# PAM2401_Tester.net
KiCad netlist of a schematic drawn in EAGLE
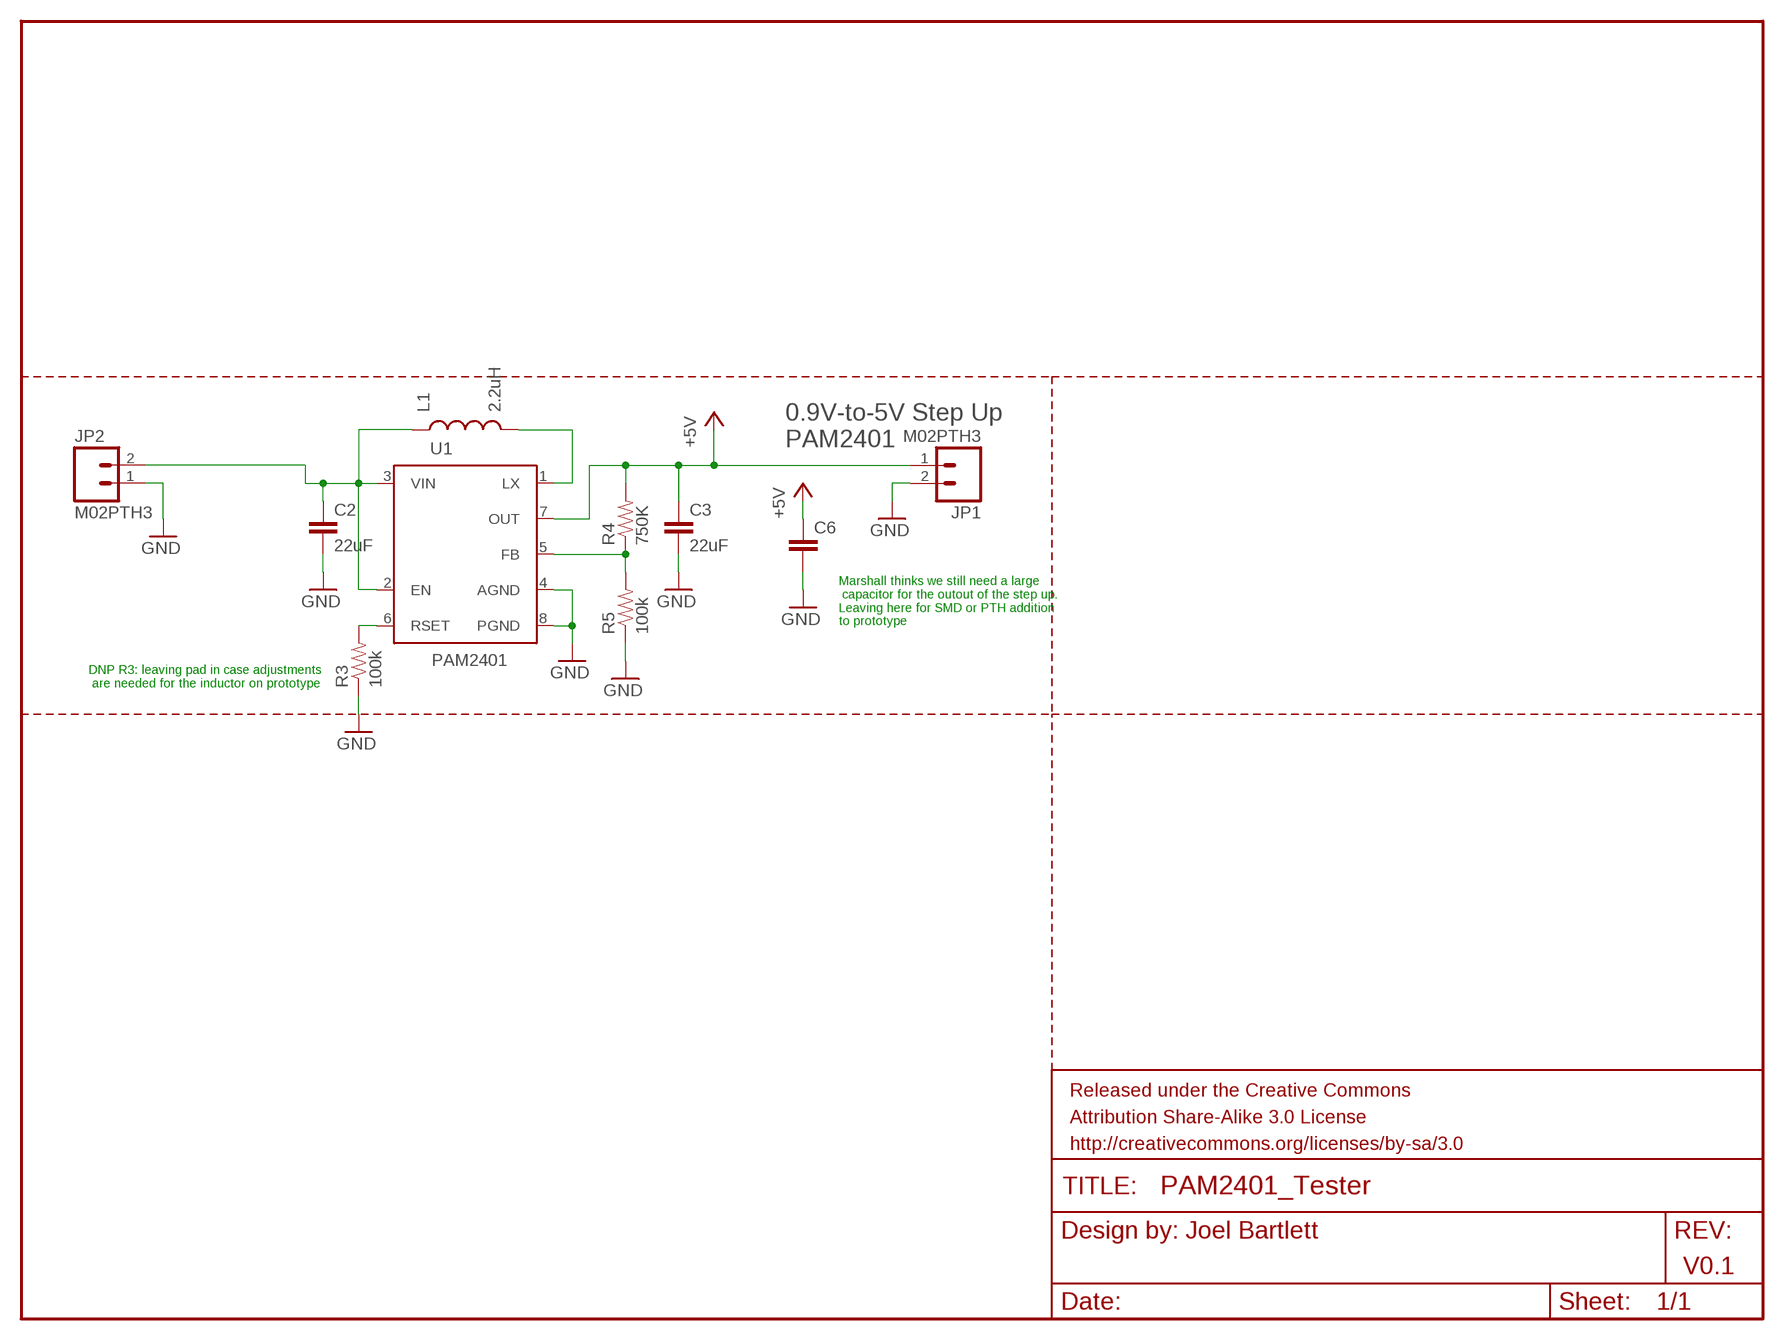
[diagram p0: schematic, sheet 1]

(export (version "E")
  (design (tool "Eeschema 10.0.6"))
  (components
    (comp (ref "C2")
      (value "22uF")
      (footprint "eagle-import:0805")
      (libsource (lib "eagle-import") (part "22UF-6.3V-20%(0805)"))
    )
    (comp (ref "C3")
      (value "22uF")
      (footprint "eagle-import:0805")
      (libsource (lib "eagle-import") (part "22UF-6.3V-20%(0805)"))
    )
    (comp (ref "C6")
      (value "CAP1206")
      (footprint "eagle-import:1206")
      (libsource (lib "eagle-import") (part "CAP1206"))
    )
    (comp (ref "FRAME1")
      (value "FRAME-LETTER")
      (footprint "eagle-import:CREATIVE_COMMONS")
      (libsource (lib "eagle-import") (part "FRAME-LETTER"))
    )
    (comp (ref "JP1")
      (value "M02PTH3")
      (footprint "eagle-import:1X02_LONGPADS")
      (libsource (lib "eagle-import") (part "M02PTH3"))
    )
    (comp (ref "JP2")
      (value "M02PTH3")
      (footprint "eagle-import:1X02_LONGPADS")
      (libsource (lib "eagle-import") (part "M02PTH3"))
    )
    (comp (ref "L1")
      (value "2.2uH")
      (footprint "eagle-import:CR54")
      (libsource (lib "eagle-import") (part "INDUCTORCR54"))
    )
    (comp (ref "R3")
      (value "100k")
      (footprint "eagle-import:0603-RES")
      (libsource (lib "eagle-import") (part "10K-1%RES-00824"))
    )
    (comp (ref "R4")
      (value "750K")
      (footprint "eagle-import:0603-RES")
      (libsource (lib "eagle-import") (part "10K-1%RES-00824"))
    )
    (comp (ref "R5")
      (value "100k")
      (footprint "eagle-import:0603-RES")
      (libsource (lib "eagle-import") (part "10K-1%RES-00824"))
    )
    (comp (ref "U1")
      (value "PAM2401")
      (footprint "eagle-import:MSOP8")
      (libsource (lib "eagle-import") (part "PAM2401"))
    )
  )
  (nets
    (net (code "1") (name "+5V") (class "Default")
      (node (ref "C3") (pin "1") (pinfunction "1_1") (pintype "passive"))
      (node (ref "C6") (pin "1") (pinfunction "1_1") (pintype "passive"))
      (node (ref "JP1") (pin "1") (pinfunction "1_1") (pintype "passive"))
      (node (ref "R4") (pin "2") (pinfunction "2_2") (pintype "passive"))
      (node (ref "U1") (pin "7") (pinfunction "OUT_7") (pintype "bidirectional"))
    )
    (net (code "2") (name "GND") (class "Default")
      (node (ref "C2") (pin "2") (pinfunction "2_2") (pintype "passive"))
      (node (ref "C3") (pin "2") (pinfunction "2_2") (pintype "passive"))
      (node (ref "C6") (pin "2") (pinfunction "2_2") (pintype "passive"))
      (node (ref "JP1") (pin "2") (pinfunction "2_2") (pintype "passive"))
      (node (ref "JP2") (pin "1") (pinfunction "1_1") (pintype "passive"))
      (node (ref "R3") (pin "1") (pinfunction "1_1") (pintype "passive"))
      (node (ref "R5") (pin "1") (pinfunction "1_1") (pintype "passive"))
      (node (ref "U1") (pin "4") (pinfunction "AGND_4") (pintype "bidirectional"))
      (node (ref "U1") (pin "8") (pinfunction "PGND_8") (pintype "bidirectional"))
    )
    (net (code "3") (name "Net-(L1-1)") (class "Default")
      (node (ref "C2") (pin "1") (pinfunction "1_1") (pintype "passive"))
      (node (ref "JP2") (pin "2") (pinfunction "2_2") (pintype "passive"))
      (node (ref "L1") (pin "P$1") (pinfunction "1_P$1") (pintype "passive"))
      (node (ref "U1") (pin "2") (pinfunction "EN_2") (pintype "bidirectional"))
      (node (ref "U1") (pin "3") (pinfunction "VIN_3") (pintype "bidirectional"))
    )
    (net (code "4") (name "Net-(L1-2)") (class "Default")
      (node (ref "L1") (pin "P$2") (pinfunction "2_P$2") (pintype "passive"))
      (node (ref "U1") (pin "1") (pinfunction "LX_1") (pintype "bidirectional"))
    )
    (net (code "5") (name "Net-(U1-FB)") (class "Default")
      (node (ref "R4") (pin "1") (pinfunction "1_1") (pintype "passive"))
      (node (ref "R5") (pin "2") (pinfunction "2_2") (pintype "passive"))
      (node (ref "U1") (pin "5") (pinfunction "FB_5") (pintype "bidirectional"))
    )
    (net (code "6") (name "Net-(U1-RSET)") (class "Default")
      (node (ref "R3") (pin "2") (pinfunction "2_2") (pintype "passive"))
      (node (ref "U1") (pin "6") (pinfunction "RSET_6") (pintype "bidirectional"))
    )
  )
)
